# BOOST_REG.net
KiCad netlist of a schematic drawn in Altium Designer
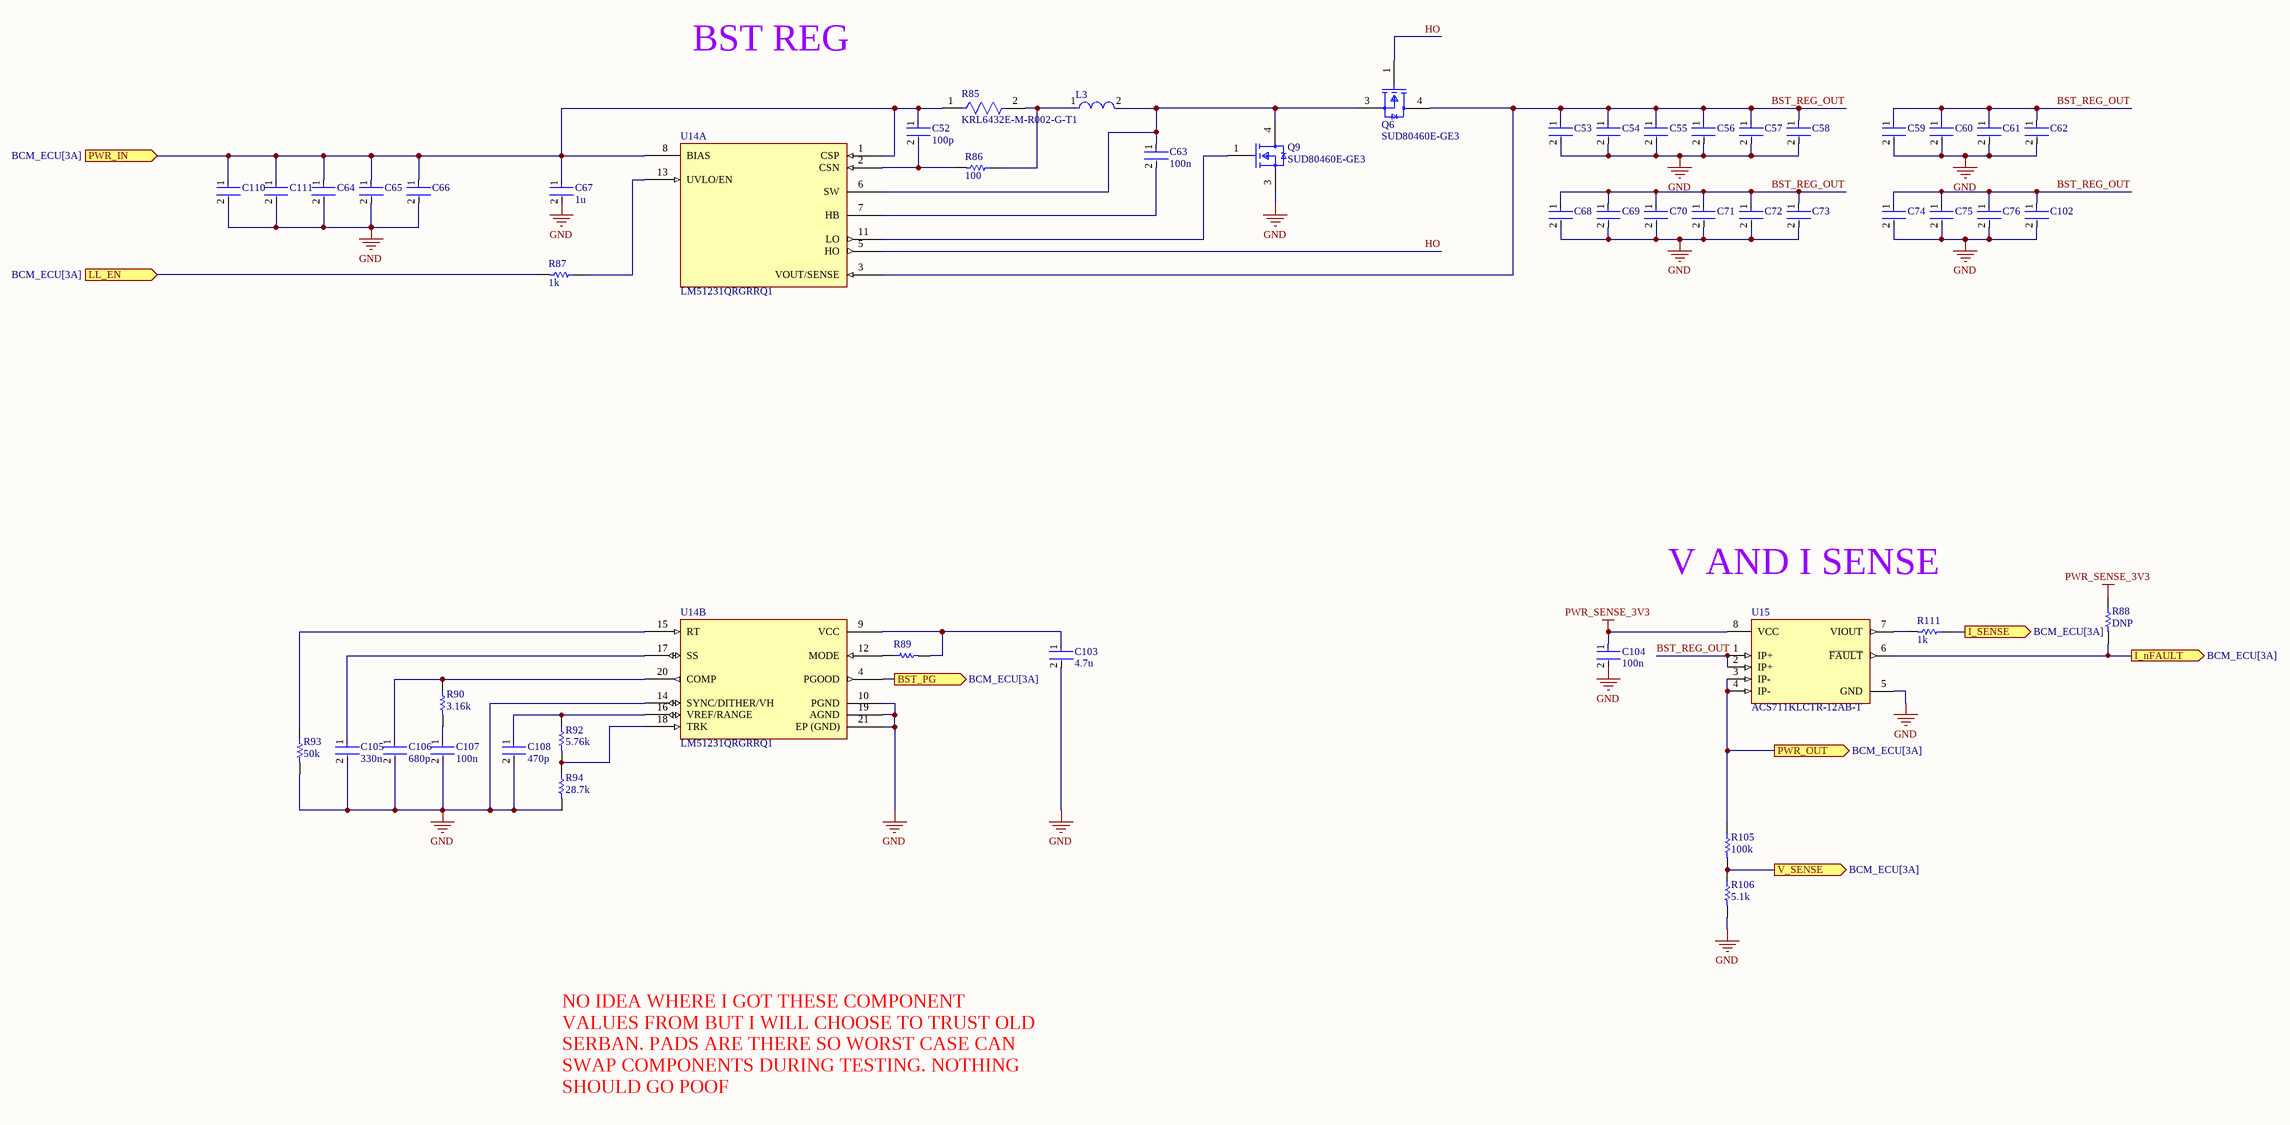
[diagram p0: BOOST_REG.SchDoc]

(export (version "E")
  (design (tool "Eeschema 10.0.6"))
  (components
    (comp (ref "C52")
      (value "100p")
      (footprint "FP-0402-L_1_0_0_05-W_0_5-IPC_A")
      (description "LARGE PADS, 0402 CAP, CHANGE COMMENT TO MATCH REAL P/N")
      (libsource (lib "Space Concordia") (part "b4654b650e69147ec39a6b967a45e02"))
    )
    (comp (ref "C53")
      (value "CGA9P3X7S2A156M250KB")
      (footprint "FP-CGA9P-IPC_B")
      (description "Cap Ceramic 15uF 100V X7S 20% Pad SMD 2220 +125°C Automotive T/R")
      (fields (field (name "TOLERANCE") "20%"))
      (libsource (lib "Altium Content Vault") (part "b4654b650e69147ec39a6b967a45e02"))
    )
    (comp (ref "C54")
      (value "CGA9P3X7S2A156M250KB")
      (footprint "FP-CGA9P-IPC_B")
      (description "Cap Ceramic 15uF 100V X7S 20% Pad SMD 2220 +125°C Automotive T/R")
      (fields (field (name "TOLERANCE") "20%"))
      (libsource (lib "Altium Content Vault") (part "b4654b650e69147ec39a6b967a45e02"))
    )
    (comp (ref "C55")
      (value "CGA9P3X7S2A156M250KB")
      (footprint "FP-CGA9P-IPC_B")
      (description "Cap Ceramic 15uF 100V X7S 20% Pad SMD 2220 +125°C Automotive T/R")
      (fields (field (name "TOLERANCE") "20%"))
      (libsource (lib "Altium Content Vault") (part "b4654b650e69147ec39a6b967a45e02"))
    )
    (comp (ref "C56")
      (value "CGA9P3X7S2A156M250KB")
      (footprint "FP-CGA9P-IPC_B")
      (description "Cap Ceramic 15uF 100V X7S 20% Pad SMD 2220 +125°C Automotive T/R")
      (fields (field (name "TOLERANCE") "20%"))
      (libsource (lib "Altium Content Vault") (part "b4654b650e69147ec39a6b967a45e02"))
    )
    (comp (ref "C57")
      (value "CGA9P3X7S2A156M250KB")
      (footprint "FP-CGA9P-IPC_B")
      (description "Cap Ceramic 15uF 100V X7S 20% Pad SMD 2220 +125°C Automotive T/R")
      (fields (field (name "TOLERANCE") "20%"))
      (libsource (lib "Altium Content Vault") (part "b4654b650e69147ec39a6b967a45e02"))
    )
    (comp (ref "C58")
      (value "CGA9P3X7S2A156M250KB")
      (footprint "FP-CGA9P-IPC_B")
      (description "Cap Ceramic 15uF 100V X7S 20% Pad SMD 2220 +125°C Automotive T/R")
      (fields (field (name "TOLERANCE") "20%"))
      (libsource (lib "Altium Content Vault") (part "b4654b650e69147ec39a6b967a45e02"))
    )
    (comp (ref "C59")
      (value "C5750X7R2A335K230KA")
      (footprint "FP-C5750-230-0_4-MFG")
      (description "Multilayer Ceramic Capacitors 3.3uF ±10% 100V X7R SMD 2220")
      (fields (field (name "VOLTAGE") "100V") (field (name "TOLERANCE") "10%"))
      (libsource (lib "Altium Content Vault") (part "02cd4be3c70576c341d710602a673aa"))
    )
    (comp (ref "C60")
      (value "C5750X7R2A335K230KA")
      (footprint "FP-C5750-230-0_4-MFG")
      (description "Multilayer Ceramic Capacitors 3.3uF ±10% 100V X7R SMD 2220")
      (fields (field (name "VOLTAGE") "100V") (field (name "TOLERANCE") "10%"))
      (libsource (lib "Altium Content Vault") (part "02cd4be3c70576c341d710602a673aa"))
    )
    (comp (ref "C61")
      (value "C5750X7R2A335K230KA")
      (footprint "FP-C5750-230-0_4-MFG")
      (description "Multilayer Ceramic Capacitors 3.3uF ±10% 100V X7R SMD 2220")
      (fields (field (name "VOLTAGE") "100V") (field (name "TOLERANCE") "10%"))
      (libsource (lib "Altium Content Vault") (part "02cd4be3c70576c341d710602a673aa"))
    )
    (comp (ref "C62")
      (value "C5750X7R2A335K230KA")
      (footprint "FP-C5750-230-0_4-MFG")
      (description "Multilayer Ceramic Capacitors 3.3uF ±10% 100V X7R SMD 2220")
      (fields (field (name "VOLTAGE") "100V") (field (name "TOLERANCE") "10%"))
      (libsource (lib "Altium Content Vault") (part "02cd4be3c70576c341d710602a673aa"))
    )
    (comp (ref "C63")
      (value "100n")
      (footprint "FP-0402-L_1_0_0_05-W_0_5-IPC_A")
      (description "LARGE PADS, 0402 CAP, CHANGE COMMENT TO MATCH REAL P/N")
      (libsource (lib "Space Concordia") (part "b4654b650e69147ec39a6b967a45e02"))
    )
    (comp (ref "C64")
      (value "CKG57NX5R1H226M500JH")
      (footprint "FP-CKG57N-MFG")
      (description "CAP CER 22UF 50V X5R SMD")
      (fields (field (name "VOLTAGE") "50V") (field (name "TOLERANCE") "20%"))
      (libsource (lib "Altium Content Vault") (part "b4654b650e69147ec39a6b967a45e02"))
    )
    (comp (ref "C65")
      (value "CKG57NX5R1H226M500JH")
      (footprint "FP-CKG57N-MFG")
      (description "CAP CER 22UF 50V X5R SMD")
      (fields (field (name "VOLTAGE") "50V") (field (name "TOLERANCE") "20%"))
      (libsource (lib "Altium Content Vault") (part "b4654b650e69147ec39a6b967a45e02"))
    )
    (comp (ref "C66")
      (value "HMK325B7105KN-T")
      (footprint "FP-1210-L_3_2_0_3-W_2_5_0-IPC_B")
      (description "None")
      (fields (field (name "TOLERANCE") "10%") (field (name "VOLTAGE") "100V"))
      (libsource (lib "Altium Content Vault") (part "02cd4be3c70576c341d710602a673aa"))
    )
    (comp (ref "C67")
      (value "1u")
      (footprint "FP-0402-L_1_0_0_05-W_0_5-IPC_A")
      (description "LARGE PADS, 0402 CAP, CHANGE COMMENT TO MATCH REAL P/N")
      (libsource (lib "Space Concordia") (part "b4654b650e69147ec39a6b967a45e02"))
    )
    (comp (ref "C68")
      (value "CGA9P3X7S2A156M250KB")
      (footprint "FP-CGA9P-IPC_B")
      (description "Cap Ceramic 15uF 100V X7S 20% Pad SMD 2220 +125°C Automotive T/R")
      (fields (field (name "TOLERANCE") "20%"))
      (libsource (lib "Altium Content Vault") (part "b4654b650e69147ec39a6b967a45e02"))
    )
    (comp (ref "C69")
      (value "CGA9P3X7S2A156M250KB")
      (footprint "FP-CGA9P-IPC_B")
      (description "Cap Ceramic 15uF 100V X7S 20% Pad SMD 2220 +125°C Automotive T/R")
      (fields (field (name "TOLERANCE") "20%"))
      (libsource (lib "Altium Content Vault") (part "b4654b650e69147ec39a6b967a45e02"))
    )
    (comp (ref "C70")
      (value "CGA9P3X7S2A156M250KB")
      (footprint "FP-CGA9P-IPC_B")
      (description "Cap Ceramic 15uF 100V X7S 20% Pad SMD 2220 +125°C Automotive T/R")
      (fields (field (name "TOLERANCE") "20%"))
      (libsource (lib "Altium Content Vault") (part "b4654b650e69147ec39a6b967a45e02"))
    )
    (comp (ref "C71")
      (value "CGA9P3X7S2A156M250KB")
      (footprint "FP-CGA9P-IPC_B")
      (description "Cap Ceramic 15uF 100V X7S 20% Pad SMD 2220 +125°C Automotive T/R")
      (fields (field (name "TOLERANCE") "20%"))
      (libsource (lib "Altium Content Vault") (part "b4654b650e69147ec39a6b967a45e02"))
    )
    (comp (ref "C72")
      (value "CGA9P3X7S2A156M250KB")
      (footprint "FP-CGA9P-IPC_B")
      (description "Cap Ceramic 15uF 100V X7S 20% Pad SMD 2220 +125°C Automotive T/R")
      (fields (field (name "TOLERANCE") "20%"))
      (libsource (lib "Altium Content Vault") (part "b4654b650e69147ec39a6b967a45e02"))
    )
    (comp (ref "C73")
      (value "CGA9P3X7S2A156M250KB")
      (footprint "FP-CGA9P-IPC_B")
      (description "Cap Ceramic 15uF 100V X7S 20% Pad SMD 2220 +125°C Automotive T/R")
      (fields (field (name "TOLERANCE") "20%"))
      (libsource (lib "Altium Content Vault") (part "b4654b650e69147ec39a6b967a45e02"))
    )
    (comp (ref "C74")
      (value "C5750X7R2A335K230KA")
      (footprint "FP-C5750-230-0_4-MFG")
      (description "Multilayer Ceramic Capacitors 3.3uF ±10% 100V X7R SMD 2220")
      (fields (field (name "VOLTAGE") "100V") (field (name "TOLERANCE") "10%"))
      (libsource (lib "Altium Content Vault") (part "02cd4be3c70576c341d710602a673aa"))
    )
    (comp (ref "C75")
      (value "C5750X7R2A335K230KA")
      (footprint "FP-C5750-230-0_4-MFG")
      (description "Multilayer Ceramic Capacitors 3.3uF ±10% 100V X7R SMD 2220")
      (fields (field (name "VOLTAGE") "100V") (field (name "TOLERANCE") "10%"))
      (libsource (lib "Altium Content Vault") (part "02cd4be3c70576c341d710602a673aa"))
    )
    (comp (ref "C76")
      (value "C5750X7R2A335K230KA")
      (footprint "FP-C5750-230-0_4-MFG")
      (description "Multilayer Ceramic Capacitors 3.3uF ±10% 100V X7R SMD 2220")
      (fields (field (name "VOLTAGE") "100V") (field (name "TOLERANCE") "10%"))
      (libsource (lib "Altium Content Vault") (part "02cd4be3c70576c341d710602a673aa"))
    )
    (comp (ref "C102")
      (value "C5750X7R2A335K230KA")
      (footprint "FP-C5750-230-0_4-MFG")
      (description "Multilayer Ceramic Capacitors 3.3uF ±10% 100V X7R SMD 2220")
      (fields (field (name "VOLTAGE") "100V") (field (name "TOLERANCE") "10%"))
      (libsource (lib "Altium Content Vault") (part "02cd4be3c70576c341d710602a673aa"))
    )
    (comp (ref "C103")
      (value "4.7u")
      (footprint "FP-0402-L_1_0_0_05-W_0_5-IPC_A")
      (description "LARGE PADS, 0402 CAP, CHANGE COMMENT TO MATCH REAL P/N")
      (libsource (lib "Space Concordia") (part "b4654b650e69147ec39a6b967a45e02"))
    )
    (comp (ref "C104")
      (value "100n")
      (footprint "FP-0402-L_1_0_0_05-W_0_5-IPC_A")
      (description "LARGE PADS, 0402 CAP, CHANGE COMMENT TO MATCH REAL P/N")
      (libsource (lib "Space Concordia") (part "b4654b650e69147ec39a6b967a45e02"))
    )
    (comp (ref "C105")
      (value "330n")
      (footprint "FP-0402-L_1_0_0_05-W_0_5-IPC_A")
      (description "LARGE PADS, 0402 CAP, CHANGE COMMENT TO MATCH REAL P/N")
      (libsource (lib "Space Concordia") (part "b4654b650e69147ec39a6b967a45e02"))
    )
    (comp (ref "C106")
      (value "680p")
      (footprint "FP-0402-L_1_0_0_05-W_0_5-IPC_A")
      (description "LARGE PADS, 0402 CAP, CHANGE COMMENT TO MATCH REAL P/N")
      (libsource (lib "Space Concordia") (part "b4654b650e69147ec39a6b967a45e02"))
    )
    (comp (ref "C107")
      (value "100n")
      (footprint "FP-0402-L_1_0_0_05-W_0_5-IPC_A")
      (description "LARGE PADS, 0402 CAP, CHANGE COMMENT TO MATCH REAL P/N")
      (libsource (lib "Space Concordia") (part "b4654b650e69147ec39a6b967a45e02"))
    )
    (comp (ref "C108")
      (value "470p")
      (footprint "FP-0402-L_1_0_0_05-W_0_5-IPC_A")
      (description "LARGE PADS, 0402 CAP, CHANGE COMMENT TO MATCH REAL P/N")
      (libsource (lib "Space Concordia") (part "b4654b650e69147ec39a6b967a45e02"))
    )
    (comp (ref "C110")
      (value "DNP")
      (footprint "FP-CKG57N-MFG")
      (description "CAP CER 22UF 50V X5R SMD")
      (fields (field (name "VOLTAGE") "50V") (field (name "TOLERANCE") "20%"))
      (libsource (lib "Altium Content Vault") (part "b4654b650e69147ec39a6b967a45e02"))
    )
    (comp (ref "C111")
      (value "DNP")
      (footprint "FP-CKG57N-MFG")
      (description "CAP CER 22UF 50V X5R SMD")
      (fields (field (name "VOLTAGE") "50V") (field (name "TOLERANCE") "20%"))
      (libsource (lib "Altium Content Vault") (part "b4654b650e69147ec39a6b967a45e02"))
    )
    (comp (ref "L3")
      (value "PM5433.302NLT")
      (footprint "PM5433.302NLT-Footprint-1")
      (description "High Current Composite Inductor - PA5433.XXXNLT and PM5433.XXXNLT")
      (libsource (lib "Space Concordia") (part "PM5433.302NLT"))
    )
    (comp (ref "Q6")
      (value "SUD80460E-GE3")
      (footprint "FP-T16-0236-MFG")
      (description "MOSFET N-CH 150V 42A TO252AA")
      (fields
        (field (name "OCTOPART") "https://octopart.com/sud80460e-ge3-vishay-78440626")
        (field (name "MANUFACTURER") "Vishay")
      )
      (libsource (lib "Altium Content Vault") (part "9dda50919618e2b74f88a68e272f5a4"))
    )
    (comp (ref "Q9")
      (value "SUD80460E-GE3")
      (footprint "FP-T16-0236-MFG")
      (description "MOSFET N-CH 150V 42A TO252AA")
      (fields
        (field (name "OCTOPART") "https://octopart.com/sud80460e-ge3-vishay-78440626")
        (field (name "MANUFACTURER") "Vishay")
      )
      (libsource (lib "Altium Content Vault") (part "9dda50919618e2b74f88a68e272f5a4"))
    )
    (comp (ref "R85")
      (value "KRL6432E-M-R002-G-T1")
      (footprint "FP-KRL6432E-MFG")
      (description "KRL6432E-M-R002-G-T1 Metal Foil Low Resistance Chip Resistor (long-side terminal), 2512, RoHS")
      (fields (field (name "TOLERANCE") "2%"))
      (libsource (lib "Altium Content Vault") (part "1029c3af85768c4190bb7ad29bc67b5"))
    )
    (comp (ref "R86")
      (value "100")
      (footprint "R0603B")
      (description "Resistor")
      (libsource (lib "Space Concordia") (part "Resistor"))
    )
    (comp (ref "R87")
      (value "1k")
      (footprint "R0603B")
      (description "Resistor")
      (libsource (lib "Space Concordia") (part "Resistor"))
    )
    (comp (ref "R88")
      (value "DNP")
      (footprint "R0603B")
      (description "Resistor")
      (libsource (lib "Space Concordia") (part "Resistor"))
    )
    (comp (ref "R89")
      (value "0402 JUMPER")
      (footprint "RESC1005X40X25ML05T05")
      (description "READ THE NAME")
      (libsource (lib "Space Concordia") (part "CMP-009-00206-2"))
    )
    (comp (ref "R90")
      (value "3.16k")
      (footprint "R0603B")
      (description "Resistor")
      (libsource (lib "Space Concordia") (part "Resistor"))
    )
    (comp (ref "R92")
      (value "5.76k")
      (footprint "R0603B")
      (description "Resistor")
      (libsource (lib "Space Concordia") (part "Resistor"))
    )
    (comp (ref "R93")
      (value "50k")
      (footprint "R0603B")
      (description "Resistor")
      (libsource (lib "Space Concordia") (part "Resistor"))
    )
    (comp (ref "R94")
      (value "28.7k")
      (footprint "R0603B")
      (description "Resistor")
      (libsource (lib "Space Concordia") (part "Resistor"))
    )
    (comp (ref "R105")
      (value "100k")
      (footprint "R0603B")
      (description "Resistor")
      (libsource (lib "Space Concordia") (part "Resistor"))
    )
    (comp (ref "R106")
      (value "5.1k")
      (footprint "R0603B")
      (description "Resistor")
      (libsource (lib "Space Concordia") (part "Resistor"))
    )
    (comp (ref "R111")
      (value "1k")
      (footprint "R0603B")
      (description "Resistor")
      (libsource (lib "Space Concordia") (part "Resistor"))
    )
    (comp (ref "U14")
      (value "LM51231QRGRRQ1")
      (footprint "QFN50P350X350X100_HS-21N")
      (description "2.2-MHz wide-VIN, synchronous boost controller with output voltage tracking 20-VQFN -40 to 125")
      (libsource (lib "Space Concordia") (part "LM51231QRGRRQ1"))
    )
    (comp (ref "U15")
      (value "ACS711KLCTR-12AB-T")
      (footprint "FP-LC-8-IPC_C")
      (description "SENSOR CURRENT HALL 12.5A AC/DC")
      (libsource (lib "Altium Content Vault") (part "b5e82308d4912bad35d89a98a7a92f9"))
    )
  )
  (nets
    (net (code "1") (name "/BST_PG") (class "Default")
      (node (ref "U14") (pin "4") (pinfunction "PGOOD_4") (pintype "output"))
    )
    (net (code "2") (name "/BST_REG_OUT") (class "Default")
      (node (ref "C102") (pin "1") (pinfunction "1_1") (pintype "passive"))
      (node (ref "C53") (pin "1") (pinfunction "1_1") (pintype "passive"))
      (node (ref "C54") (pin "1") (pinfunction "1_1") (pintype "passive"))
      (node (ref "C55") (pin "1") (pinfunction "1_1") (pintype "passive"))
      (node (ref "C56") (pin "1") (pinfunction "1_1") (pintype "passive"))
      (node (ref "C57") (pin "1") (pinfunction "1_1") (pintype "passive"))
      (node (ref "C58") (pin "1") (pinfunction "1_1") (pintype "passive"))
      (node (ref "C59") (pin "1") (pinfunction "1_1") (pintype "passive"))
      (node (ref "C60") (pin "1") (pinfunction "1_1") (pintype "passive"))
      (node (ref "C61") (pin "1") (pinfunction "1_1") (pintype "passive"))
      (node (ref "C62") (pin "1") (pinfunction "1_1") (pintype "passive"))
      (node (ref "C68") (pin "1") (pinfunction "1_1") (pintype "passive"))
      (node (ref "C69") (pin "1") (pinfunction "1_1") (pintype "passive"))
      (node (ref "C70") (pin "1") (pinfunction "1_1") (pintype "passive"))
      (node (ref "C71") (pin "1") (pinfunction "1_1") (pintype "passive"))
      (node (ref "C72") (pin "1") (pinfunction "1_1") (pintype "passive"))
      (node (ref "C73") (pin "1") (pinfunction "1_1") (pintype "passive"))
      (node (ref "C74") (pin "1") (pinfunction "1_1") (pintype "passive"))
      (node (ref "C75") (pin "1") (pinfunction "1_1") (pintype "passive"))
      (node (ref "C76") (pin "1") (pinfunction "1_1") (pintype "passive"))
      (node (ref "Q6") (pin "4") (pinfunction "D_4") (pintype "passive"))
      (node (ref "U14") (pin "3") (pinfunction "VOUT/SENSE_3") (pintype "input"))
      (node (ref "U15") (pin "1") (pinfunction "IP+_1") (pintype "input"))
      (node (ref "U15") (pin "2") (pinfunction "IP+_2") (pintype "input"))
    )
    (net (code "3") (name "/HO") (class "Default")
      (node (ref "Q6") (pin "1") (pinfunction "G_1") (pintype "passive"))
      (node (ref "U14") (pin "5") (pinfunction "HO_5") (pintype "output"))
    )
    (net (code "4") (name "/I_SENSE") (class "Default")
      (node (ref "R111") (pin "1") (pinfunction "1_1") (pintype "passive"))
    )
    (net (code "5") (name "/I_nFAULT") (class "Default")
      (node (ref "R88") (pin "2") (pinfunction "2_2") (pintype "passive"))
      (node (ref "U15") (pin "6") (pinfunction "~{FAULT}_6") (pintype "output"))
    )
    (net (code "6") (name "/LL_EN") (class "Default")
      (node (ref "R87") (pin "2") (pinfunction "2_2") (pintype "passive"))
    )
    (net (code "7") (name "/PWR_IN") (class "Default")
      (node (ref "C110") (pin "1") (pinfunction "1_1") (pintype "passive"))
      (node (ref "C111") (pin "1") (pinfunction "1_1") (pintype "passive"))
      (node (ref "C52") (pin "1") (pinfunction "1_1") (pintype "passive"))
      (node (ref "C64") (pin "1") (pinfunction "1_1") (pintype "passive"))
      (node (ref "C65") (pin "1") (pinfunction "1_1") (pintype "passive"))
      (node (ref "C66") (pin "1") (pinfunction "1_1") (pintype "passive"))
      (node (ref "C67") (pin "1") (pinfunction "1_1") (pintype "passive"))
      (node (ref "R85") (pin "1") (pinfunction "1_1") (pintype "passive"))
      (node (ref "U14") (pin "1") (pinfunction "CSP_1") (pintype "input"))
      (node (ref "U14") (pin "8") (pinfunction "BIAS_8") (pintype "power_in"))
    )
    (net (code "8") (name "/PWR_OUT") (class "Default")
      (node (ref "R105") (pin "1") (pinfunction "1_1") (pintype "passive"))
      (node (ref "U15") (pin "3") (pinfunction "IP-_3") (pintype "input"))
      (node (ref "U15") (pin "4") (pinfunction "IP-_4") (pintype "input"))
    )
    (net (code "9") (name "/V_SENSE") (class "Default")
      (node (ref "R105") (pin "2") (pinfunction "2_2") (pintype "passive"))
      (node (ref "R106") (pin "1") (pinfunction "1_1") (pintype "passive"))
    )
    (net (code "10") (name "GND") (class "Default")
      (node (ref "C102") (pin "2") (pinfunction "2_2") (pintype "passive"))
      (node (ref "C103") (pin "2") (pinfunction "2_2") (pintype "passive"))
      (node (ref "C104") (pin "2") (pinfunction "2_2") (pintype "passive"))
      (node (ref "C105") (pin "2") (pinfunction "2_2") (pintype "passive"))
      (node (ref "C106") (pin "2") (pinfunction "2_2") (pintype "passive"))
      (node (ref "C107") (pin "2") (pinfunction "2_2") (pintype "passive"))
      (node (ref "C108") (pin "2") (pinfunction "2_2") (pintype "passive"))
      (node (ref "C110") (pin "2") (pinfunction "2_2") (pintype "passive"))
      (node (ref "C111") (pin "2") (pinfunction "2_2") (pintype "passive"))
      (node (ref "C53") (pin "2") (pinfunction "2_2") (pintype "passive"))
      (node (ref "C54") (pin "2") (pinfunction "2_2") (pintype "passive"))
      (node (ref "C55") (pin "2") (pinfunction "2_2") (pintype "passive"))
      (node (ref "C56") (pin "2") (pinfunction "2_2") (pintype "passive"))
      (node (ref "C57") (pin "2") (pinfunction "2_2") (pintype "passive"))
      (node (ref "C58") (pin "2") (pinfunction "2_2") (pintype "passive"))
      (node (ref "C59") (pin "2") (pinfunction "2_2") (pintype "passive"))
      (node (ref "C60") (pin "2") (pinfunction "2_2") (pintype "passive"))
      (node (ref "C61") (pin "2") (pinfunction "2_2") (pintype "passive"))
      (node (ref "C62") (pin "2") (pinfunction "2_2") (pintype "passive"))
      (node (ref "C64") (pin "2") (pinfunction "2_2") (pintype "passive"))
      (node (ref "C65") (pin "2") (pinfunction "2_2") (pintype "passive"))
      (node (ref "C66") (pin "2") (pinfunction "2_2") (pintype "passive"))
      (node (ref "C67") (pin "2") (pinfunction "2_2") (pintype "passive"))
      (node (ref "C68") (pin "2") (pinfunction "2_2") (pintype "passive"))
      (node (ref "C69") (pin "2") (pinfunction "2_2") (pintype "passive"))
      (node (ref "C70") (pin "2") (pinfunction "2_2") (pintype "passive"))
      (node (ref "C71") (pin "2") (pinfunction "2_2") (pintype "passive"))
      (node (ref "C72") (pin "2") (pinfunction "2_2") (pintype "passive"))
      (node (ref "C73") (pin "2") (pinfunction "2_2") (pintype "passive"))
      (node (ref "C74") (pin "2") (pinfunction "2_2") (pintype "passive"))
      (node (ref "C75") (pin "2") (pinfunction "2_2") (pintype "passive"))
      (node (ref "C76") (pin "2") (pinfunction "2_2") (pintype "passive"))
      (node (ref "Q9") (pin "3") (pinfunction "S_3") (pintype "passive"))
      (node (ref "R106") (pin "2") (pinfunction "2_2") (pintype "passive"))
      (node (ref "R93") (pin "2") (pinfunction "2_2") (pintype "passive"))
      (node (ref "R94") (pin "2") (pinfunction "2_2") (pintype "passive"))
      (node (ref "U14") (pin "10") (pinfunction "PGND_10") (pintype "passive"))
      (node (ref "U14") (pin "14") (pinfunction "SYNC/DITHER/VH_14") (pintype "bidirectional"))
      (node (ref "U14") (pin "19") (pinfunction "AGND_19") (pintype "passive"))
      (node (ref "U14") (pin "21") (pinfunction "EP_(GND)_21") (pintype "passive"))
      (node (ref "U15") (pin "5") (pinfunction "GND_5") (pintype "power_in"))
    )
    (net (code "11") (name "Net-(C107-Pad1)") (class "Default")
      (node (ref "C107") (pin "1") (pinfunction "1_1") (pintype "passive"))
      (node (ref "R90") (pin "2") (pinfunction "2_2") (pintype "passive"))
    )
    (net (code "12") (name "Net-(L3-Pad1)") (class "Default")
      (node (ref "L3") (pin "1") (pinfunction "1_1") (pintype "passive"))
      (node (ref "R85") (pin "2") (pinfunction "2_2") (pintype "passive"))
      (node (ref "R86") (pin "1") (pinfunction "1_1") (pintype "passive"))
    )
    (net (code "13") (name "Net-(Q6-S)") (class "Default")
      (node (ref "C63") (pin "1") (pinfunction "1_1") (pintype "passive"))
      (node (ref "L3") (pin "2") (pinfunction "2_2") (pintype "passive"))
      (node (ref "Q6") (pin "3") (pinfunction "S_3") (pintype "passive"))
      (node (ref "Q9") (pin "4") (pinfunction "D_4") (pintype "passive"))
      (node (ref "U14") (pin "6") (pinfunction "SW_6") (pintype "power_in"))
    )
    (net (code "14") (name "Net-(Q9-G)") (class "Default")
      (node (ref "Q9") (pin "1") (pinfunction "G_1") (pintype "passive"))
      (node (ref "U14") (pin "11") (pinfunction "LO_11") (pintype "output"))
    )
    (net (code "15") (name "Net-(U14A-CSN)") (class "Default")
      (node (ref "C52") (pin "2") (pinfunction "2_2") (pintype "passive"))
      (node (ref "R86") (pin "2") (pinfunction "2_2") (pintype "passive"))
      (node (ref "U14") (pin "2") (pinfunction "CSN_2") (pintype "input"))
    )
    (net (code "16") (name "Net-(U14A-HB)") (class "Default")
      (node (ref "C63") (pin "2") (pinfunction "2_2") (pintype "passive"))
      (node (ref "U14") (pin "7") (pinfunction "HB_7") (pintype "power_in"))
    )
    (net (code "17") (name "Net-(U14A-UVLO{slash}EN)") (class "Default")
      (node (ref "R87") (pin "1") (pinfunction "1_1") (pintype "passive"))
      (node (ref "U14") (pin "13") (pinfunction "UVLO/EN_13") (pintype "input"))
    )
    (net (code "18") (name "Net-(U14B-COMP)") (class "Default")
      (node (ref "C106") (pin "1") (pinfunction "1_1") (pintype "passive"))
      (node (ref "R90") (pin "1") (pinfunction "1_1") (pintype "passive"))
      (node (ref "U14") (pin "20") (pinfunction "COMP_20") (pintype "output"))
    )
    (net (code "19") (name "Net-(U14B-MODE)") (class "Default")
      (node (ref "R89") (pin "1") (pinfunction "1_1") (pintype "passive"))
      (node (ref "U14") (pin "12") (pinfunction "MODE_12") (pintype "input"))
    )
    (net (code "20") (name "Net-(U14B-RT)") (class "Default")
      (node (ref "R93") (pin "1") (pinfunction "1_1") (pintype "passive"))
      (node (ref "U14") (pin "15") (pinfunction "RT_15") (pintype "input"))
    )
    (net (code "21") (name "Net-(U14B-SS)") (class "Default")
      (node (ref "C105") (pin "1") (pinfunction "1_1") (pintype "passive"))
      (node (ref "U14") (pin "17") (pinfunction "SS_17") (pintype "bidirectional"))
    )
    (net (code "22") (name "Net-(U14B-TRK)") (class "Default")
      (node (ref "R92") (pin "2") (pinfunction "2_2") (pintype "passive"))
      (node (ref "R94") (pin "1") (pinfunction "1_1") (pintype "passive"))
      (node (ref "U14") (pin "18") (pinfunction "TRK_18") (pintype "input"))
    )
    (net (code "23") (name "Net-(U14B-VCC)") (class "Default")
      (node (ref "C103") (pin "1") (pinfunction "1_1") (pintype "passive"))
      (node (ref "R89") (pin "2") (pinfunction "2_2") (pintype "passive"))
      (node (ref "U14") (pin "9") (pinfunction "VCC_9") (pintype "power_in"))
    )
    (net (code "24") (name "Net-(U14B-VREF{slash}RANGE)") (class "Default")
      (node (ref "C108") (pin "1") (pinfunction "1_1") (pintype "passive"))
      (node (ref "R92") (pin "1") (pinfunction "1_1") (pintype "passive"))
      (node (ref "U14") (pin "16") (pinfunction "VREF/RANGE_16") (pintype "bidirectional"))
    )
    (net (code "25") (name "Net-(U15-VIOUT)") (class "Default")
      (node (ref "R111") (pin "2") (pinfunction "2_2") (pintype "passive"))
      (node (ref "U15") (pin "7") (pinfunction "VIOUT_7") (pintype "output"))
    )
    (net (code "26") (name "PWR_SENSE_3V3") (class "Default")
      (node (ref "C104") (pin "1") (pinfunction "1_1") (pintype "passive"))
      (node (ref "R88") (pin "1") (pinfunction "1_1") (pintype "passive"))
      (node (ref "U15") (pin "8") (pinfunction "VCC_8") (pintype "power_in"))
    )
  )
)
